# targetController.net
KiCad netlist of a schematic drawn in EAGLE
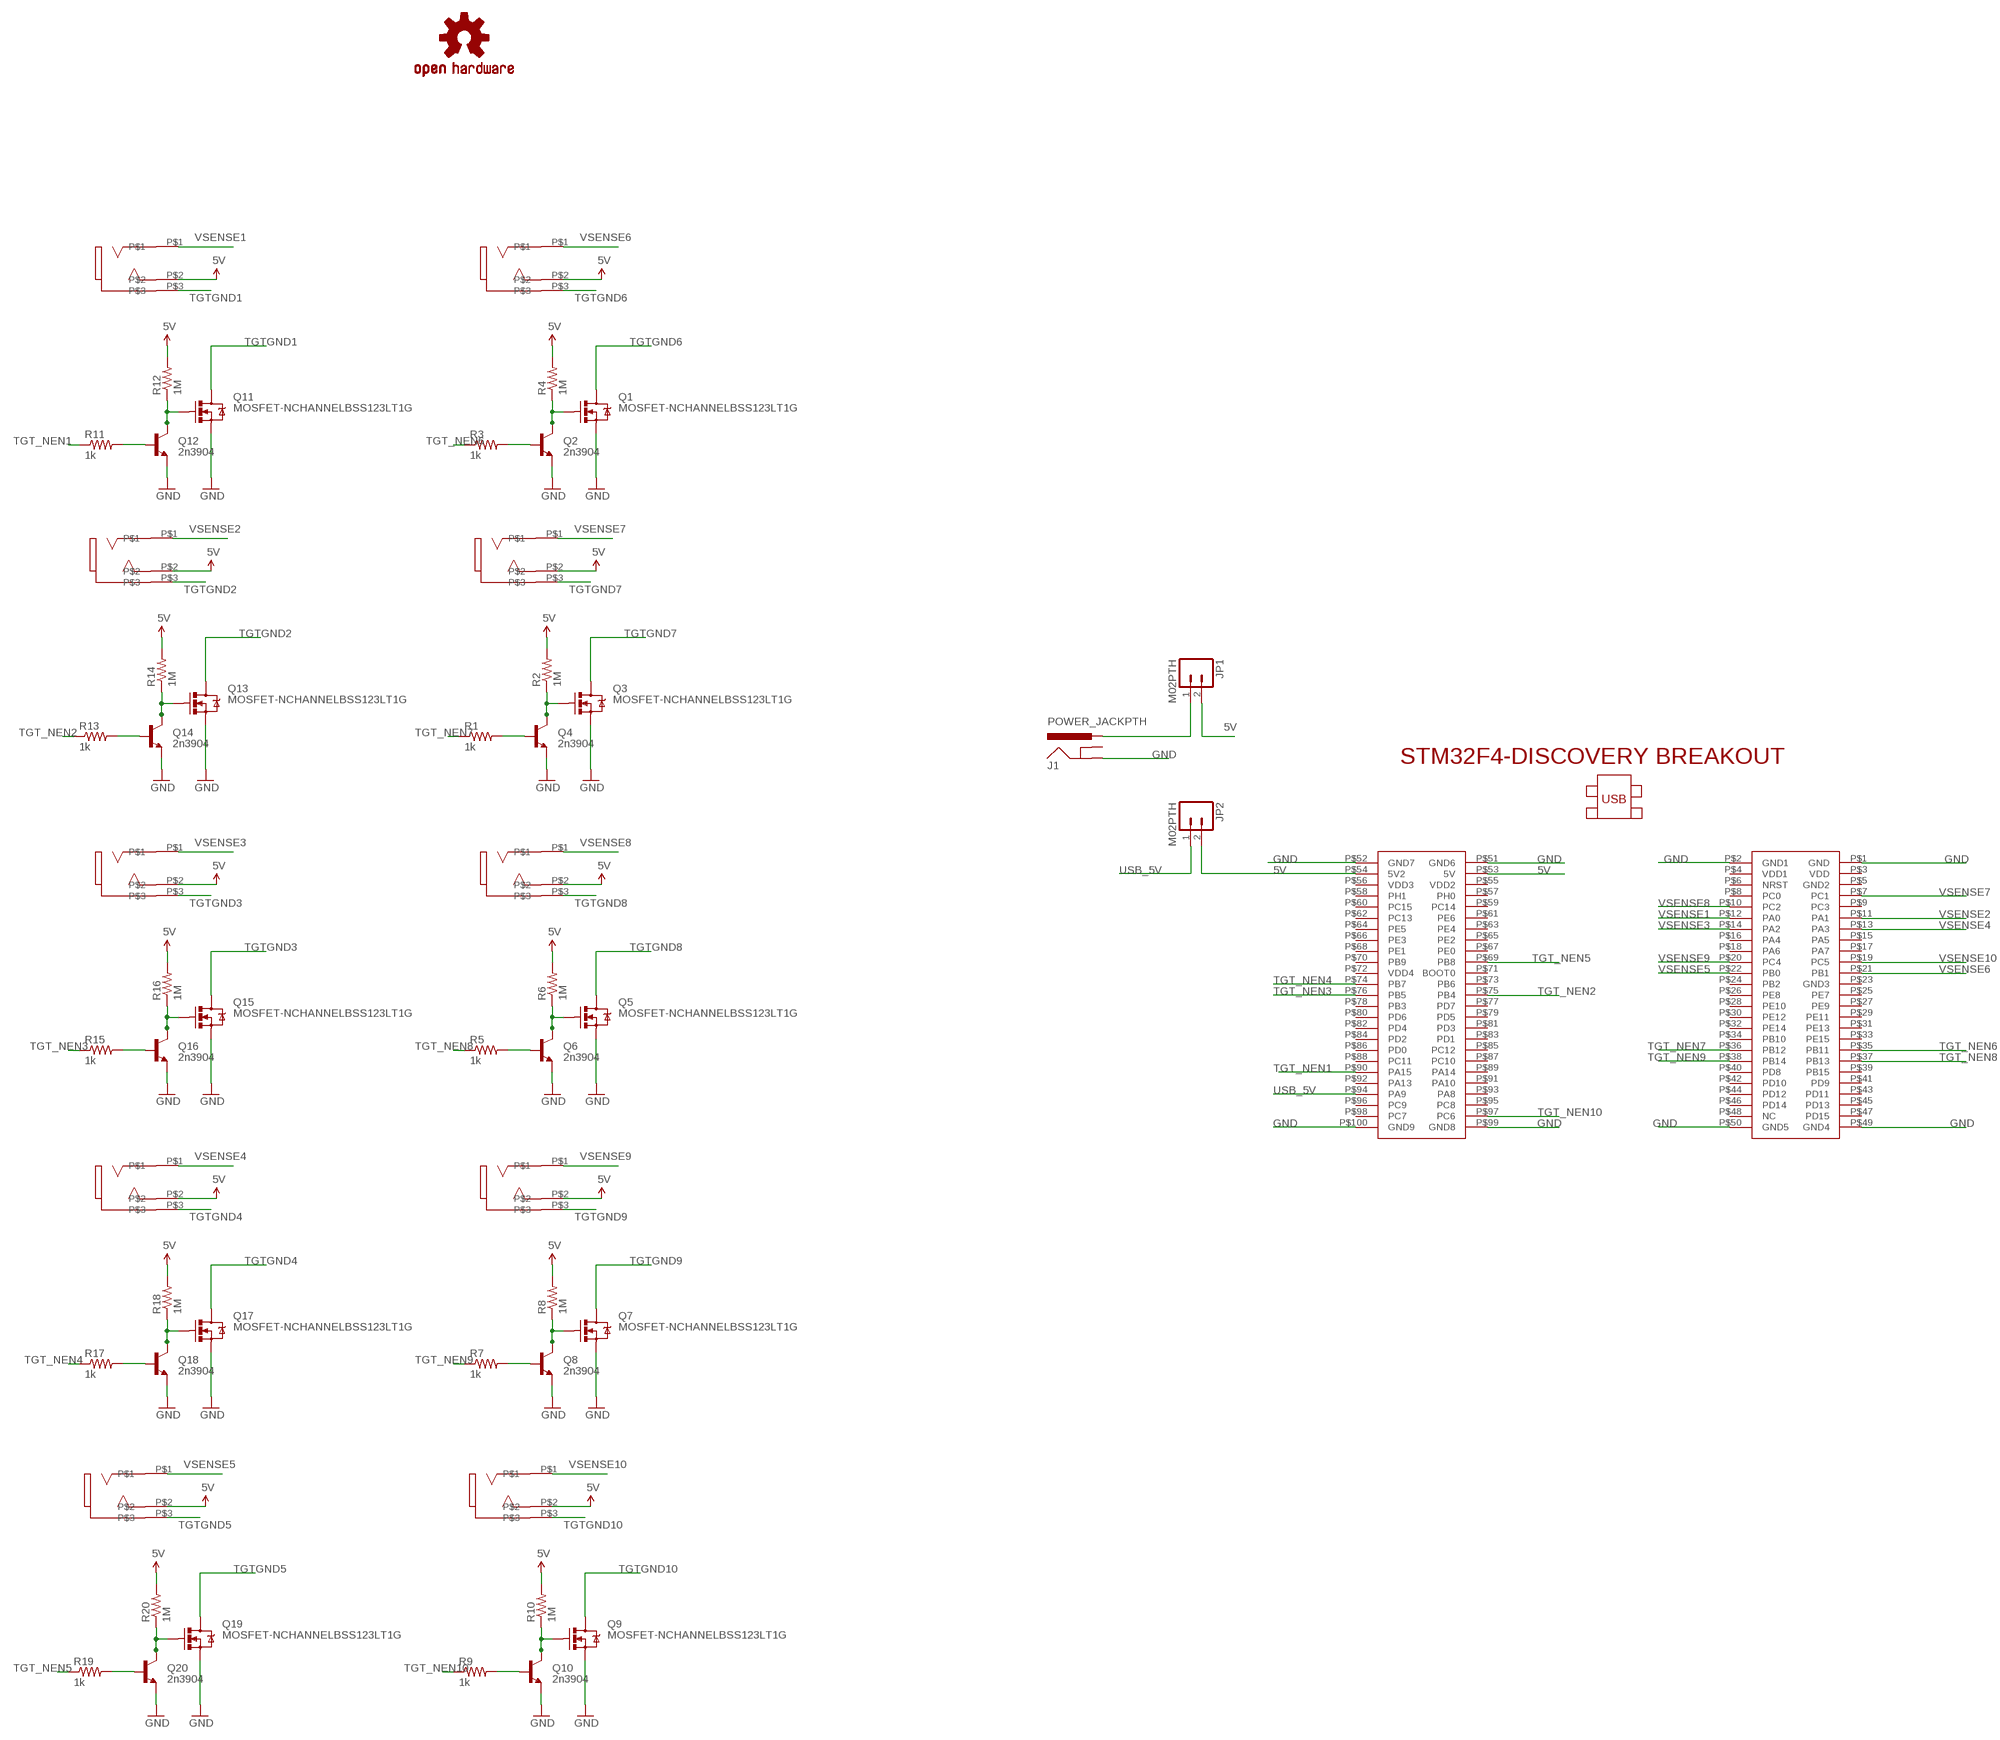
[diagram p0: schematic, sheet 1]

(export (version "E")
  (design (tool "Eeschema 10.0.6"))
  (components
    (comp (ref "J1")
      (value "POWER_JACKPTH")
      (footprint "eagle-import:POWER_JACK_PTH")
      (libsource (lib "eagle-import") (part "POWER_JACKPTH"))
    )
    (comp (ref "JP1")
      (value "M02PTH")
      (footprint "eagle-import:1X02")
      (libsource (lib "eagle-import") (part "M02PTH"))
    )
    (comp (ref "JP2")
      (value "M02PTH")
      (footprint "eagle-import:1X02")
      (libsource (lib "eagle-import") (part "M02PTH"))
    )
    (comp (ref "LOGO1")
      (value "OSHW-LOGOS")
      (footprint "eagle-import:OSHW-LOGO-S")
      (libsource (lib "eagle-import") (part "OSHW-LOGOS"))
    )
    (comp (ref "Q1")
      (value "MOSFET-NCHANNELBSS123LT1G")
      (footprint "eagle-import:SOT23")
      (libsource (lib "eagle-import") (part "MOSFET-NCHANNELBSS123LT1G"))
    )
    (comp (ref "Q2")
      (value "2n3904")
      (footprint "eagle-import:SOT23-3")
      (libsource (lib "eagle-import") (part "TRANSISTOR_NPNSOT23-3"))
    )
    (comp (ref "Q3")
      (value "MOSFET-NCHANNELBSS123LT1G")
      (footprint "eagle-import:SOT23")
      (libsource (lib "eagle-import") (part "MOSFET-NCHANNELBSS123LT1G"))
    )
    (comp (ref "Q4")
      (value "2n3904")
      (footprint "eagle-import:SOT23-3")
      (libsource (lib "eagle-import") (part "TRANSISTOR_NPNSOT23-3"))
    )
    (comp (ref "Q5")
      (value "MOSFET-NCHANNELBSS123LT1G")
      (footprint "eagle-import:SOT23")
      (libsource (lib "eagle-import") (part "MOSFET-NCHANNELBSS123LT1G"))
    )
    (comp (ref "Q6")
      (value "2n3904")
      (footprint "eagle-import:SOT23-3")
      (libsource (lib "eagle-import") (part "TRANSISTOR_NPNSOT23-3"))
    )
    (comp (ref "Q7")
      (value "MOSFET-NCHANNELBSS123LT1G")
      (footprint "eagle-import:SOT23")
      (libsource (lib "eagle-import") (part "MOSFET-NCHANNELBSS123LT1G"))
    )
    (comp (ref "Q8")
      (value "2n3904")
      (footprint "eagle-import:SOT23-3")
      (libsource (lib "eagle-import") (part "TRANSISTOR_NPNSOT23-3"))
    )
    (comp (ref "Q9")
      (value "MOSFET-NCHANNELBSS123LT1G")
      (footprint "eagle-import:SOT23")
      (libsource (lib "eagle-import") (part "MOSFET-NCHANNELBSS123LT1G"))
    )
    (comp (ref "Q10")
      (value "2n3904")
      (footprint "eagle-import:SOT23-3")
      (libsource (lib "eagle-import") (part "TRANSISTOR_NPNSOT23-3"))
    )
    (comp (ref "Q11")
      (value "MOSFET-NCHANNELBSS123LT1G")
      (footprint "eagle-import:SOT23")
      (libsource (lib "eagle-import") (part "MOSFET-NCHANNELBSS123LT1G"))
    )
    (comp (ref "Q12")
      (value "2n3904")
      (footprint "eagle-import:SOT23-3")
      (libsource (lib "eagle-import") (part "TRANSISTOR_NPNSOT23-3"))
    )
    (comp (ref "Q13")
      (value "MOSFET-NCHANNELBSS123LT1G")
      (footprint "eagle-import:SOT23")
      (libsource (lib "eagle-import") (part "MOSFET-NCHANNELBSS123LT1G"))
    )
    (comp (ref "Q14")
      (value "2n3904")
      (footprint "eagle-import:SOT23-3")
      (libsource (lib "eagle-import") (part "TRANSISTOR_NPNSOT23-3"))
    )
    (comp (ref "Q15")
      (value "MOSFET-NCHANNELBSS123LT1G")
      (footprint "eagle-import:SOT23")
      (libsource (lib "eagle-import") (part "MOSFET-NCHANNELBSS123LT1G"))
    )
    (comp (ref "Q16")
      (value "2n3904")
      (footprint "eagle-import:SOT23-3")
      (libsource (lib "eagle-import") (part "TRANSISTOR_NPNSOT23-3"))
    )
    (comp (ref "Q17")
      (value "MOSFET-NCHANNELBSS123LT1G")
      (footprint "eagle-import:SOT23")
      (libsource (lib "eagle-import") (part "MOSFET-NCHANNELBSS123LT1G"))
    )
    (comp (ref "Q18")
      (value "2n3904")
      (footprint "eagle-import:SOT23-3")
      (libsource (lib "eagle-import") (part "TRANSISTOR_NPNSOT23-3"))
    )
    (comp (ref "Q19")
      (value "MOSFET-NCHANNELBSS123LT1G")
      (footprint "eagle-import:SOT23")
      (libsource (lib "eagle-import") (part "MOSFET-NCHANNELBSS123LT1G"))
    )
    (comp (ref "Q20")
      (value "2n3904")
      (footprint "eagle-import:SOT23-3")
      (libsource (lib "eagle-import") (part "TRANSISTOR_NPNSOT23-3"))
    )
    (comp (ref "R1")
      (value "1k")
      (footprint "eagle-import:0805")
      (libsource (lib "eagle-import") (part "RESISTOR0805-RES"))
    )
    (comp (ref "R2")
      (value "1M")
      (footprint "eagle-import:0805")
      (libsource (lib "eagle-import") (part "RESISTOR0805-RES"))
    )
    (comp (ref "R3")
      (value "1k")
      (footprint "eagle-import:0805")
      (libsource (lib "eagle-import") (part "RESISTOR0805-RES"))
    )
    (comp (ref "R4")
      (value "1M")
      (footprint "eagle-import:0805")
      (libsource (lib "eagle-import") (part "RESISTOR0805-RES"))
    )
    (comp (ref "R5")
      (value "1k")
      (footprint "eagle-import:0805")
      (libsource (lib "eagle-import") (part "RESISTOR0805-RES"))
    )
    (comp (ref "R6")
      (value "1M")
      (footprint "eagle-import:0805")
      (libsource (lib "eagle-import") (part "RESISTOR0805-RES"))
    )
    (comp (ref "R7")
      (value "1k")
      (footprint "eagle-import:0805")
      (libsource (lib "eagle-import") (part "RESISTOR0805-RES"))
    )
    (comp (ref "R8")
      (value "1M")
      (footprint "eagle-import:0805")
      (libsource (lib "eagle-import") (part "RESISTOR0805-RES"))
    )
    (comp (ref "R9")
      (value "1k")
      (footprint "eagle-import:0805")
      (libsource (lib "eagle-import") (part "RESISTOR0805-RES"))
    )
    (comp (ref "R10")
      (value "1M")
      (footprint "eagle-import:0805")
      (libsource (lib "eagle-import") (part "RESISTOR0805-RES"))
    )
    (comp (ref "R11")
      (value "1k")
      (footprint "eagle-import:0805")
      (libsource (lib "eagle-import") (part "RESISTOR0805-RES"))
    )
    (comp (ref "R12")
      (value "1M")
      (footprint "eagle-import:0805")
      (libsource (lib "eagle-import") (part "RESISTOR0805-RES"))
    )
    (comp (ref "R13")
      (value "1k")
      (footprint "eagle-import:0805")
      (libsource (lib "eagle-import") (part "RESISTOR0805-RES"))
    )
    (comp (ref "R14")
      (value "1M")
      (footprint "eagle-import:0805")
      (libsource (lib "eagle-import") (part "RESISTOR0805-RES"))
    )
    (comp (ref "R15")
      (value "1k")
      (footprint "eagle-import:0805")
      (libsource (lib "eagle-import") (part "RESISTOR0805-RES"))
    )
    (comp (ref "R16")
      (value "1M")
      (footprint "eagle-import:0805")
      (libsource (lib "eagle-import") (part "RESISTOR0805-RES"))
    )
    (comp (ref "R17")
      (value "1k")
      (footprint "eagle-import:0805")
      (libsource (lib "eagle-import") (part "RESISTOR0805-RES"))
    )
    (comp (ref "R18")
      (value "1M")
      (footprint "eagle-import:0805")
      (libsource (lib "eagle-import") (part "RESISTOR0805-RES"))
    )
    (comp (ref "R19")
      (value "1k")
      (footprint "eagle-import:0805")
      (libsource (lib "eagle-import") (part "RESISTOR0805-RES"))
    )
    (comp (ref "R20")
      (value "1M")
      (footprint "eagle-import:0805")
      (libsource (lib "eagle-import") (part "RESISTOR0805-RES"))
    )
    (comp (ref "T1")
      (value "35RASMT2BHNTRX")
      (footprint "eagle-import:35RASMT2BHNTRX")
      (libsource (lib "eagle-import") (part "35RASMT2BHNTRX"))
    )
    (comp (ref "T2")
      (value "35RASMT2BHNTRX")
      (footprint "eagle-import:35RASMT2BHNTRX")
      (libsource (lib "eagle-import") (part "35RASMT2BHNTRX"))
    )
    (comp (ref "T3")
      (value "35RASMT2BHNTRX")
      (footprint "eagle-import:35RASMT2BHNTRX")
      (libsource (lib "eagle-import") (part "35RASMT2BHNTRX"))
    )
    (comp (ref "T4")
      (value "35RASMT2BHNTRX")
      (footprint "eagle-import:35RASMT2BHNTRX")
      (libsource (lib "eagle-import") (part "35RASMT2BHNTRX"))
    )
    (comp (ref "T5")
      (value "35RASMT2BHNTRX")
      (footprint "eagle-import:35RASMT2BHNTRX")
      (libsource (lib "eagle-import") (part "35RASMT2BHNTRX"))
    )
    (comp (ref "T6")
      (value "35RASMT2BHNTRX")
      (footprint "eagle-import:35RASMT2BHNTRX")
      (libsource (lib "eagle-import") (part "35RASMT2BHNTRX"))
    )
    (comp (ref "T7")
      (value "35RASMT2BHNTRX")
      (footprint "eagle-import:35RASMT2BHNTRX")
      (libsource (lib "eagle-import") (part "35RASMT2BHNTRX"))
    )
    (comp (ref "T8")
      (value "35RASMT2BHNTRX")
      (footprint "eagle-import:35RASMT2BHNTRX")
      (libsource (lib "eagle-import") (part "35RASMT2BHNTRX"))
    )
    (comp (ref "T9")
      (value "35RASMT2BHNTRX")
      (footprint "eagle-import:35RASMT2BHNTRX")
      (libsource (lib "eagle-import") (part "35RASMT2BHNTRX"))
    )
    (comp (ref "T10")
      (value "35RASMT2BHNTRX")
      (footprint "eagle-import:35RASMT2BHNTRX")
      (libsource (lib "eagle-import") (part "35RASMT2BHNTRX"))
    )
    (comp (ref "U$1")
      (value "STM32F4-DISCOVERY")
      (footprint "eagle-import:STM32F4-DISCOVERY")
      (libsource (lib "eagle-import") (part "STM32F4-DISCOVERY"))
    )
  )
  (nets
    (net (code "1") (name "/TGTGND1") (class "Default")
      (node (ref "Q11") (pin "3") (pinfunction "D_3") (pintype "passive"))
      (node (ref "T1") (pin "P$3") (pinfunction "P$3_P$3") (pintype "bidirectional"))
    )
    (net (code "2") (name "/TGTGND2") (class "Default")
      (node (ref "Q13") (pin "3") (pinfunction "D_3") (pintype "passive"))
      (node (ref "T2") (pin "P$3") (pinfunction "P$3_P$3") (pintype "bidirectional"))
    )
    (net (code "3") (name "/TGTGND3") (class "Default")
      (node (ref "Q15") (pin "3") (pinfunction "D_3") (pintype "passive"))
      (node (ref "T3") (pin "P$3") (pinfunction "P$3_P$3") (pintype "bidirectional"))
    )
    (net (code "4") (name "/TGTGND4") (class "Default")
      (node (ref "Q17") (pin "3") (pinfunction "D_3") (pintype "passive"))
      (node (ref "T4") (pin "P$3") (pinfunction "P$3_P$3") (pintype "bidirectional"))
    )
    (net (code "5") (name "/TGTGND5") (class "Default")
      (node (ref "Q19") (pin "3") (pinfunction "D_3") (pintype "passive"))
      (node (ref "T5") (pin "P$3") (pinfunction "P$3_P$3") (pintype "bidirectional"))
    )
    (net (code "6") (name "/TGTGND6") (class "Default")
      (node (ref "Q1") (pin "3") (pinfunction "D_3") (pintype "passive"))
      (node (ref "T6") (pin "P$3") (pinfunction "P$3_P$3") (pintype "bidirectional"))
    )
    (net (code "7") (name "/TGTGND7") (class "Default")
      (node (ref "Q3") (pin "3") (pinfunction "D_3") (pintype "passive"))
      (node (ref "T7") (pin "P$3") (pinfunction "P$3_P$3") (pintype "bidirectional"))
    )
    (net (code "8") (name "/TGTGND8") (class "Default")
      (node (ref "Q5") (pin "3") (pinfunction "D_3") (pintype "passive"))
      (node (ref "T8") (pin "P$3") (pinfunction "P$3_P$3") (pintype "bidirectional"))
    )
    (net (code "9") (name "/TGTGND9") (class "Default")
      (node (ref "Q7") (pin "3") (pinfunction "D_3") (pintype "passive"))
      (node (ref "T9") (pin "P$3") (pinfunction "P$3_P$3") (pintype "bidirectional"))
    )
    (net (code "10") (name "/TGTGND10") (class "Default")
      (node (ref "Q9") (pin "3") (pinfunction "D_3") (pintype "passive"))
      (node (ref "T10") (pin "P$3") (pinfunction "P$3_P$3") (pintype "bidirectional"))
    )
    (net (code "11") (name "/TGT_NEN1") (class "Default")
      (node (ref "R11") (pin "1") (pinfunction "1_1") (pintype "passive"))
      (node (ref "U$1") (pin "P$90") (pinfunction "PA15_P$90") (pintype "bidirectional"))
    )
    (net (code "12") (name "/TGT_NEN2") (class "Default")
      (node (ref "R13") (pin "1") (pinfunction "1_1") (pintype "passive"))
      (node (ref "U$1") (pin "P$75") (pinfunction "PB4_P$75") (pintype "bidirectional"))
    )
    (net (code "13") (name "/TGT_NEN3") (class "Default")
      (node (ref "R15") (pin "1") (pinfunction "1_1") (pintype "passive"))
      (node (ref "U$1") (pin "P$76") (pinfunction "PB5_P$76") (pintype "bidirectional"))
    )
    (net (code "14") (name "/TGT_NEN4") (class "Default")
      (node (ref "R17") (pin "1") (pinfunction "1_1") (pintype "passive"))
      (node (ref "U$1") (pin "P$74") (pinfunction "PB7_P$74") (pintype "bidirectional"))
    )
    (net (code "15") (name "/TGT_NEN5") (class "Default")
      (node (ref "R19") (pin "1") (pinfunction "1_1") (pintype "passive"))
      (node (ref "U$1") (pin "P$69") (pinfunction "PB8_P$69") (pintype "bidirectional"))
    )
    (net (code "16") (name "/TGT_NEN6") (class "Default")
      (node (ref "R3") (pin "1") (pinfunction "1_1") (pintype "passive"))
      (node (ref "U$1") (pin "P$35") (pinfunction "PB11_P$35") (pintype "bidirectional"))
    )
    (net (code "17") (name "/TGT_NEN7") (class "Default")
      (node (ref "R1") (pin "1") (pinfunction "1_1") (pintype "passive"))
      (node (ref "U$1") (pin "P$36") (pinfunction "PB12_P$36") (pintype "bidirectional"))
    )
    (net (code "18") (name "/TGT_NEN8") (class "Default")
      (node (ref "R5") (pin "1") (pinfunction "1_1") (pintype "passive"))
      (node (ref "U$1") (pin "P$37") (pinfunction "PB13_P$37") (pintype "bidirectional"))
    )
    (net (code "19") (name "/TGT_NEN9") (class "Default")
      (node (ref "R7") (pin "1") (pinfunction "1_1") (pintype "passive"))
      (node (ref "U$1") (pin "P$38") (pinfunction "PB14_P$38") (pintype "bidirectional"))
    )
    (net (code "20") (name "/TGT_NEN10") (class "Default")
      (node (ref "R9") (pin "1") (pinfunction "1_1") (pintype "passive"))
      (node (ref "U$1") (pin "P$97") (pinfunction "PC6_P$97") (pintype "bidirectional"))
    )
    (net (code "21") (name "/USB_5V") (class "Default")
      (node (ref "JP2") (pin "1") (pinfunction "1_1") (pintype "passive"))
      (node (ref "U$1") (pin "P$94") (pinfunction "PA9_P$94") (pintype "bidirectional"))
    )
    (net (code "22") (name "/VSENSE1") (class "Default")
      (node (ref "T1") (pin "P$1") (pinfunction "P$1_P$1") (pintype "bidirectional"))
      (node (ref "U$1") (pin "P$12") (pinfunction "PA0_P$12") (pintype "bidirectional"))
    )
    (net (code "23") (name "/VSENSE2") (class "Default")
      (node (ref "T2") (pin "P$1") (pinfunction "P$1_P$1") (pintype "bidirectional"))
      (node (ref "U$1") (pin "P$11") (pinfunction "PA1_P$11") (pintype "bidirectional"))
    )
    (net (code "24") (name "/VSENSE3") (class "Default")
      (node (ref "T3") (pin "P$1") (pinfunction "P$1_P$1") (pintype "bidirectional"))
      (node (ref "U$1") (pin "P$14") (pinfunction "PA2_P$14") (pintype "bidirectional"))
    )
    (net (code "25") (name "/VSENSE4") (class "Default")
      (node (ref "T4") (pin "P$1") (pinfunction "P$1_P$1") (pintype "bidirectional"))
      (node (ref "U$1") (pin "P$13") (pinfunction "PA3_P$13") (pintype "bidirectional"))
    )
    (net (code "26") (name "/VSENSE5") (class "Default")
      (node (ref "T5") (pin "P$1") (pinfunction "P$1_P$1") (pintype "bidirectional"))
      (node (ref "U$1") (pin "P$22") (pinfunction "PB0_P$22") (pintype "bidirectional"))
    )
    (net (code "27") (name "/VSENSE6") (class "Default")
      (node (ref "T6") (pin "P$1") (pinfunction "P$1_P$1") (pintype "bidirectional"))
      (node (ref "U$1") (pin "P$21") (pinfunction "PB1_P$21") (pintype "bidirectional"))
    )
    (net (code "28") (name "/VSENSE7") (class "Default")
      (node (ref "T7") (pin "P$1") (pinfunction "P$1_P$1") (pintype "bidirectional"))
      (node (ref "U$1") (pin "P$7") (pinfunction "PC1_P$7") (pintype "bidirectional"))
    )
    (net (code "29") (name "/VSENSE8") (class "Default")
      (node (ref "T8") (pin "P$1") (pinfunction "P$1_P$1") (pintype "bidirectional"))
      (node (ref "U$1") (pin "P$10") (pinfunction "PC2_P$10") (pintype "bidirectional"))
    )
    (net (code "30") (name "/VSENSE9") (class "Default")
      (node (ref "T9") (pin "P$1") (pinfunction "P$1_P$1") (pintype "bidirectional"))
      (node (ref "U$1") (pin "P$20") (pinfunction "PC4_P$20") (pintype "bidirectional"))
    )
    (net (code "31") (name "/VSENSE10") (class "Default")
      (node (ref "T10") (pin "P$1") (pinfunction "P$1_P$1") (pintype "bidirectional"))
      (node (ref "U$1") (pin "P$19") (pinfunction "PC5_P$19") (pintype "bidirectional"))
    )
    (net (code "32") (name "5V") (class "Default")
      (node (ref "JP1") (pin "2") (pinfunction "2_2") (pintype "passive"))
      (node (ref "JP2") (pin "2") (pinfunction "2_2") (pintype "passive"))
      (node (ref "R10") (pin "2") (pinfunction "2_2") (pintype "passive"))
      (node (ref "R12") (pin "2") (pinfunction "2_2") (pintype "passive"))
      (node (ref "R14") (pin "2") (pinfunction "2_2") (pintype "passive"))
      (node (ref "R16") (pin "2") (pinfunction "2_2") (pintype "passive"))
      (node (ref "R18") (pin "2") (pinfunction "2_2") (pintype "passive"))
      (node (ref "R2") (pin "2") (pinfunction "2_2") (pintype "passive"))
      (node (ref "R20") (pin "2") (pinfunction "2_2") (pintype "passive"))
      (node (ref "R4") (pin "2") (pinfunction "2_2") (pintype "passive"))
      (node (ref "R6") (pin "2") (pinfunction "2_2") (pintype "passive"))
      (node (ref "R8") (pin "2") (pinfunction "2_2") (pintype "passive"))
      (node (ref "T1") (pin "P$2") (pinfunction "P$2_P$2") (pintype "bidirectional"))
      (node (ref "T10") (pin "P$2") (pinfunction "P$2_P$2") (pintype "bidirectional"))
      (node (ref "T2") (pin "P$2") (pinfunction "P$2_P$2") (pintype "bidirectional"))
      (node (ref "T3") (pin "P$2") (pinfunction "P$2_P$2") (pintype "bidirectional"))
      (node (ref "T4") (pin "P$2") (pinfunction "P$2_P$2") (pintype "bidirectional"))
      (node (ref "T5") (pin "P$2") (pinfunction "P$2_P$2") (pintype "bidirectional"))
      (node (ref "T6") (pin "P$2") (pinfunction "P$2_P$2") (pintype "bidirectional"))
      (node (ref "T7") (pin "P$2") (pinfunction "P$2_P$2") (pintype "bidirectional"))
      (node (ref "T8") (pin "P$2") (pinfunction "P$2_P$2") (pintype "bidirectional"))
      (node (ref "T9") (pin "P$2") (pinfunction "P$2_P$2") (pintype "bidirectional"))
      (node (ref "U$1") (pin "P$53") (pinfunction "5V_P$53") (pintype "bidirectional"))
      (node (ref "U$1") (pin "P$54") (pinfunction "5V2_P$54") (pintype "bidirectional"))
    )
    (net (code "33") (name "GND") (class "Default")
      (node (ref "J1") (pin "GND") (pinfunction "GND_GND") (pintype "bidirectional"))
      (node (ref "Q1") (pin "2") (pinfunction "S_2") (pintype "passive"))
      (node (ref "Q10") (pin "2") (pinfunction "E_2") (pintype "passive"))
      (node (ref "Q11") (pin "2") (pinfunction "S_2") (pintype "passive"))
      (node (ref "Q12") (pin "2") (pinfunction "E_2") (pintype "passive"))
      (node (ref "Q13") (pin "2") (pinfunction "S_2") (pintype "passive"))
      (node (ref "Q14") (pin "2") (pinfunction "E_2") (pintype "passive"))
      (node (ref "Q15") (pin "2") (pinfunction "S_2") (pintype "passive"))
      (node (ref "Q16") (pin "2") (pinfunction "E_2") (pintype "passive"))
      (node (ref "Q17") (pin "2") (pinfunction "S_2") (pintype "passive"))
      (node (ref "Q18") (pin "2") (pinfunction "E_2") (pintype "passive"))
      (node (ref "Q19") (pin "2") (pinfunction "S_2") (pintype "passive"))
      (node (ref "Q2") (pin "2") (pinfunction "E_2") (pintype "passive"))
      (node (ref "Q20") (pin "2") (pinfunction "E_2") (pintype "passive"))
      (node (ref "Q3") (pin "2") (pinfunction "S_2") (pintype "passive"))
      (node (ref "Q4") (pin "2") (pinfunction "E_2") (pintype "passive"))
      (node (ref "Q5") (pin "2") (pinfunction "S_2") (pintype "passive"))
      (node (ref "Q6") (pin "2") (pinfunction "E_2") (pintype "passive"))
      (node (ref "Q7") (pin "2") (pinfunction "S_2") (pintype "passive"))
      (node (ref "Q8") (pin "2") (pinfunction "E_2") (pintype "passive"))
      (node (ref "Q9") (pin "2") (pinfunction "S_2") (pintype "passive"))
      (node (ref "U$1") (pin "P$1") (pinfunction "GND_P$1") (pintype "bidirectional"))
      (node (ref "U$1") (pin "P$100") (pinfunction "GND9_P$100") (pintype "bidirectional"))
      (node (ref "U$1") (pin "P$2") (pinfunction "GND1_P$2") (pintype "bidirectional"))
      (node (ref "U$1") (pin "P$49") (pinfunction "GND4_P$49") (pintype "bidirectional"))
      (node (ref "U$1") (pin "P$50") (pinfunction "GND5_P$50") (pintype "bidirectional"))
      (node (ref "U$1") (pin "P$51") (pinfunction "GND6_P$51") (pintype "bidirectional"))
      (node (ref "U$1") (pin "P$52") (pinfunction "GND7_P$52") (pintype "bidirectional"))
      (node (ref "U$1") (pin "P$99") (pinfunction "GND8_P$99") (pintype "bidirectional"))
    )
    (net (code "34") (name "Net-(J1-PadPWR)") (class "Default")
      (node (ref "J1") (pin "PWR") (pinfunction "PWR_PWR") (pintype "bidirectional"))
      (node (ref "JP1") (pin "1") (pinfunction "1_1") (pintype "passive"))
    )
    (net (code "35") (name "Net-(Q1-G)") (class "Default")
      (node (ref "Q1") (pin "1") (pinfunction "G_1") (pintype "passive"))
      (node (ref "Q2") (pin "3") (pinfunction "C_3") (pintype "passive"))
      (node (ref "R4") (pin "1") (pinfunction "1_1") (pintype "passive"))
    )
    (net (code "36") (name "Net-(Q2-B)") (class "Default")
      (node (ref "Q2") (pin "1") (pinfunction "B_1") (pintype "passive"))
      (node (ref "R3") (pin "2") (pinfunction "2_2") (pintype "passive"))
    )
    (net (code "37") (name "Net-(Q3-G)") (class "Default")
      (node (ref "Q3") (pin "1") (pinfunction "G_1") (pintype "passive"))
      (node (ref "Q4") (pin "3") (pinfunction "C_3") (pintype "passive"))
      (node (ref "R2") (pin "1") (pinfunction "1_1") (pintype "passive"))
    )
    (net (code "38") (name "Net-(Q4-B)") (class "Default")
      (node (ref "Q4") (pin "1") (pinfunction "B_1") (pintype "passive"))
      (node (ref "R1") (pin "2") (pinfunction "2_2") (pintype "passive"))
    )
    (net (code "39") (name "Net-(Q5-G)") (class "Default")
      (node (ref "Q5") (pin "1") (pinfunction "G_1") (pintype "passive"))
      (node (ref "Q6") (pin "3") (pinfunction "C_3") (pintype "passive"))
      (node (ref "R6") (pin "1") (pinfunction "1_1") (pintype "passive"))
    )
    (net (code "40") (name "Net-(Q6-B)") (class "Default")
      (node (ref "Q6") (pin "1") (pinfunction "B_1") (pintype "passive"))
      (node (ref "R5") (pin "2") (pinfunction "2_2") (pintype "passive"))
    )
    (net (code "41") (name "Net-(Q7-G)") (class "Default")
      (node (ref "Q7") (pin "1") (pinfunction "G_1") (pintype "passive"))
      (node (ref "Q8") (pin "3") (pinfunction "C_3") (pintype "passive"))
      (node (ref "R8") (pin "1") (pinfunction "1_1") (pintype "passive"))
    )
    (net (code "42") (name "Net-(Q8-B)") (class "Default")
      (node (ref "Q8") (pin "1") (pinfunction "B_1") (pintype "passive"))
      (node (ref "R7") (pin "2") (pinfunction "2_2") (pintype "passive"))
    )
    (net (code "43") (name "Net-(Q10-B)") (class "Default")
      (node (ref "Q10") (pin "1") (pinfunction "B_1") (pintype "passive"))
      (node (ref "R9") (pin "2") (pinfunction "2_2") (pintype "passive"))
    )
    (net (code "44") (name "Net-(Q10-C)") (class "Default")
      (node (ref "Q10") (pin "3") (pinfunction "C_3") (pintype "passive"))
      (node (ref "Q9") (pin "1") (pinfunction "G_1") (pintype "passive"))
      (node (ref "R10") (pin "1") (pinfunction "1_1") (pintype "passive"))
    )
    (net (code "45") (name "Net-(Q11-G)") (class "Default")
      (node (ref "Q11") (pin "1") (pinfunction "G_1") (pintype "passive"))
      (node (ref "Q12") (pin "3") (pinfunction "C_3") (pintype "passive"))
      (node (ref "R12") (pin "1") (pinfunction "1_1") (pintype "passive"))
    )
    (net (code "46") (name "Net-(Q12-B)") (class "Default")
      (node (ref "Q12") (pin "1") (pinfunction "B_1") (pintype "passive"))
      (node (ref "R11") (pin "2") (pinfunction "2_2") (pintype "passive"))
    )
    (net (code "47") (name "Net-(Q13-G)") (class "Default")
      (node (ref "Q13") (pin "1") (pinfunction "G_1") (pintype "passive"))
      (node (ref "Q14") (pin "3") (pinfunction "C_3") (pintype "passive"))
      (node (ref "R14") (pin "1") (pinfunction "1_1") (pintype "passive"))
    )
    (net (code "48") (name "Net-(Q14-B)") (class "Default")
      (node (ref "Q14") (pin "1") (pinfunction "B_1") (pintype "passive"))
      (node (ref "R13") (pin "2") (pinfunction "2_2") (pintype "passive"))
    )
    (net (code "49") (name "Net-(Q15-G)") (class "Default")
      (node (ref "Q15") (pin "1") (pinfunction "G_1") (pintype "passive"))
      (node (ref "Q16") (pin "3") (pinfunction "C_3") (pintype "passive"))
      (node (ref "R16") (pin "1") (pinfunction "1_1") (pintype "passive"))
    )
    (net (code "50") (name "Net-(Q16-B)") (class "Default")
      (node (ref "Q16") (pin "1") (pinfunction "B_1") (pintype "passive"))
      (node (ref "R15") (pin "2") (pinfunction "2_2") (pintype "passive"))
    )
    (net (code "51") (name "Net-(Q17-G)") (class "Default")
      (node (ref "Q17") (pin "1") (pinfunction "G_1") (pintype "passive"))
      (node (ref "Q18") (pin "3") (pinfunction "C_3") (pintype "passive"))
      (node (ref "R18") (pin "1") (pinfunction "1_1") (pintype "passive"))
    )
    (net (code "52") (name "Net-(Q18-B)") (class "Default")
      (node (ref "Q18") (pin "1") (pinfunction "B_1") (pintype "passive"))
      (node (ref "R17") (pin "2") (pinfunction "2_2") (pintype "passive"))
    )
    (net (code "53") (name "Net-(Q19-G)") (class "Default")
      (node (ref "Q19") (pin "1") (pinfunction "G_1") (pintype "passive"))
      (node (ref "Q20") (pin "3") (pinfunction "C_3") (pintype "passive"))
      (node (ref "R20") (pin "1") (pinfunction "1_1") (pintype "passive"))
    )
    (net (code "54") (name "Net-(Q20-B)") (class "Default")
      (node (ref "Q20") (pin "1") (pinfunction "B_1") (pintype "passive"))
      (node (ref "R19") (pin "2") (pinfunction "2_2") (pintype "passive"))
    )
    (net (code "55") (name "unconnected-(J1-PadGNDBREAK)") (class "Default")
      (node (ref "J1") (pin "GNDBREAK") (pinfunction "GNDBREAK_GNDBREAK") (pintype "bidirectional"))
    )
    (net (code "56") (name "unconnected-(U$1-BOOT0-PadP$71)") (class "Default")
      (node (ref "U$1") (pin "P$71") (pinfunction "BOOT0_P$71") (pintype "bidirectional"))
    )
    (net (code "57") (name "unconnected-(U$1-GND2-PadP$5)") (class "Default")
      (node (ref "U$1") (pin "P$5") (pinfunction "GND2_P$5") (pintype "bidirectional"))
    )
    (net (code "58") (name "unconnected-(U$1-GND3-PadP$23)") (class "Default")
      (node (ref "U$1") (pin "P$23") (pinfunction "GND3_P$23") (pintype "bidirectional"))
    )
    (net (code "59") (name "unconnected-(U$1-NC-PadP$48)") (class "Default")
      (node (ref "U$1") (pin "P$48") (pinfunction "NC_P$48") (pintype "bidirectional"))
    )
    (net (code "60") (name "unconnected-(U$1-NRST-PadP$6)") (class "Default")
      (node (ref "U$1") (pin "P$6") (pinfunction "NRST_P$6") (pintype "bidirectional"))
    )
    (net (code "61") (name "unconnected-(U$1-PA4-PadP$16)") (class "Default")
      (node (ref "U$1") (pin "P$16") (pinfunction "PA4_P$16") (pintype "bidirectional"))
    )
    (net (code "62") (name "unconnected-(U$1-PA5-PadP$15)") (class "Default")
      (node (ref "U$1") (pin "P$15") (pinfunction "PA5_P$15") (pintype "bidirectional"))
    )
    (net (code "63") (name "unconnected-(U$1-PA6-PadP$18)") (class "Default")
      (node (ref "U$1") (pin "P$18") (pinfunction "PA6_P$18") (pintype "bidirectional"))
    )
    (net (code "64") (name "unconnected-(U$1-PA7-PadP$17)") (class "Default")
      (node (ref "U$1") (pin "P$17") (pinfunction "PA7_P$17") (pintype "bidirectional"))
    )
    (net (code "65") (name "unconnected-(U$1-PA8-PadP$93)") (class "Default")
      (node (ref "U$1") (pin "P$93") (pinfunction "PA8_P$93") (pintype "bidirectional"))
    )
    (net (code "66") (name "unconnected-(U$1-PA10-PadP$91)") (class "Default")
      (node (ref "U$1") (pin "P$91") (pinfunction "PA10_P$91") (pintype "bidirectional"))
    )
    (net (code "67") (name "unconnected-(U$1-PA13-PadP$92)") (class "Default")
      (node (ref "U$1") (pin "P$92") (pinfunction "PA13_P$92") (pintype "bidirectional"))
    )
    (net (code "68") (name "unconnected-(U$1-PA14-PadP$89)") (class "Default")
      (node (ref "U$1") (pin "P$89") (pinfunction "PA14_P$89") (pintype "bidirectional"))
    )
    (net (code "69") (name "unconnected-(U$1-PB2-PadP$24)") (class "Default")
      (node (ref "U$1") (pin "P$24") (pinfunction "PB2_P$24") (pintype "bidirectional"))
    )
    (net (code "70") (name "unconnected-(U$1-PB3-PadP$78)") (class "Default")
      (node (ref "U$1") (pin "P$78") (pinfunction "PB3_P$78") (pintype "bidirectional"))
    )
    (net (code "71") (name "unconnected-(U$1-PB6-PadP$73)") (class "Default")
      (node (ref "U$1") (pin "P$73") (pinfunction "PB6_P$73") (pintype "bidirectional"))
    )
    (net (code "72") (name "unconnected-(U$1-PB9-PadP$70)") (class "Default")
      (node (ref "U$1") (pin "P$70") (pinfunction "PB9_P$70") (pintype "bidirectional"))
    )
    (net (code "73") (name "unconnected-(U$1-PB10-PadP$34)") (class "Default")
      (node (ref "U$1") (pin "P$34") (pinfunction "PB10_P$34") (pintype "bidirectional"))
    )
    (net (code "74") (name "unconnected-(U$1-PB15-PadP$39)") (class "Default")
      (node (ref "U$1") (pin "P$39") (pinfunction "PB15_P$39") (pintype "bidirectional"))
    )
    (net (code "75") (name "unconnected-(U$1-PC0-PadP$8)") (class "Default")
      (node (ref "U$1") (pin "P$8") (pinfunction "PC0_P$8") (pintype "bidirectional"))
    )
    (net (code "76") (name "unconnected-(U$1-PC3-PadP$9)") (class "Default")
      (node (ref "U$1") (pin "P$9") (pinfunction "PC3_P$9") (pintype "bidirectional"))
    )
    (net (code "77") (name "unconnected-(U$1-PC7-PadP$98)") (class "Default")
      (node (ref "U$1") (pin "P$98") (pinfunction "PC7_P$98") (pintype "bidirectional"))
    )
    (net (code "78") (name "unconnected-(U$1-PC8-PadP$95)") (class "Default")
      (node (ref "U$1") (pin "P$95") (pinfunction "PC8_P$95") (pintype "bidirectional"))
    )
    (net (code "79") (name "unconnected-(U$1-PC9-PadP$96)") (class "Default")
      (node (ref "U$1") (pin "P$96") (pinfunction "PC9_P$96") (pintype "bidirectional"))
    )
    (net (code "80") (name "unconnected-(U$1-PC10-PadP$87)") (class "Default")
      (node (ref "U$1") (pin "P$87") (pinfunction "PC10_P$87") (pintype "bidirectional"))
    )
    (net (code "81") (name "unconnected-(U$1-PC11-PadP$88)") (class "Default")
      (node (ref "U$1") (pin "P$88") (pinfunction "PC11_P$88") (pintype "bidirectional"))
    )
    (net (code "82") (name "unconnected-(U$1-PC12-PadP$85)") (class "Default")
      (node (ref "U$1") (pin "P$85") (pinfunction "PC12_P$85") (pintype "bidirectional"))
    )
    (net (code "83") (name "unconnected-(U$1-PC13-PadP$62)") (class "Default")
      (node (ref "U$1") (pin "P$62") (pinfunction "PC13_P$62") (pintype "bidirectional"))
    )
    (net (code "84") (name "unconnected-(U$1-PC14-PadP$59)") (class "Default")
      (node (ref "U$1") (pin "P$59") (pinfunction "PC14_P$59") (pintype "bidirectional"))
    )
    (net (code "85") (name "unconnected-(U$1-PC15-PadP$60)") (class "Default")
      (node (ref "U$1") (pin "P$60") (pinfunction "PC15_P$60") (pintype "bidirectional"))
    )
    (net (code "86") (name "unconnected-(U$1-PD0-PadP$86)") (class "Default")
      (node (ref "U$1") (pin "P$86") (pinfunction "PD0_P$86") (pintype "bidirectional"))
    )
    (net (code "87") (name "unconnected-(U$1-PD1-PadP$83)") (class "Default")
      (node (ref "U$1") (pin "P$83") (pinfunction "PD1_P$83") (pintype "bidirectional"))
    )
    (net (code "88") (name "unconnected-(U$1-PD2-PadP$84)") (class "Default")
      (node (ref "U$1") (pin "P$84") (pinfunction "PD2_P$84") (pintype "bidirectional"))
    )
    (net (code "89") (name "unconnected-(U$1-PD3-PadP$81)") (class "Default")
      (node (ref "U$1") (pin "P$81") (pinfunction "PD3_P$81") (pintype "bidirectional"))
    )
    (net (code "90") (name "unconnected-(U$1-PD4-PadP$82)") (class "Default")
      (node (ref "U$1") (pin "P$82") (pinfunction "PD4_P$82") (pintype "bidirectional"))
    )
    (net (code "91") (name "unconnected-(U$1-PD5-PadP$79)") (class "Default")
      (node (ref "U$1") (pin "P$79") (pinfunction "PD5_P$79") (pintype "bidirectional"))
    )
    (net (code "92") (name "unconnected-(U$1-PD6-PadP$80)") (class "Default")
      (node (ref "U$1") (pin "P$80") (pinfunction "PD6_P$80") (pintype "bidirectional"))
    )
    (net (code "93") (name "unconnected-(U$1-PD7-PadP$77)") (class "Default")
      (node (ref "U$1") (pin "P$77") (pinfunction "PD7_P$77") (pintype "bidirectional"))
    )
    (net (code "94") (name "unconnected-(U$1-PD8-PadP$40)") (class "Default")
      (node (ref "U$1") (pin "P$40") (pinfunction "PD8_P$40") (pintype "bidirectional"))
    )
    (net (code "95") (name "unconnected-(U$1-PD9-PadP$41)") (class "Default")
      (node (ref "U$1") (pin "P$41") (pinfunction "PD9_P$41") (pintype "bidirectional"))
    )
    (net (code "96") (name "unconnected-(U$1-PD10-PadP$42)") (class "Default")
      (node (ref "U$1") (pin "P$42") (pinfunction "PD10_P$42") (pintype "bidirectional"))
    )
    (net (code "97") (name "unconnected-(U$1-PD11-PadP$43)") (class "Default")
      (node (ref "U$1") (pin "P$43") (pinfunction "PD11_P$43") (pintype "bidirectional"))
    )
    (net (code "98") (name "unconnected-(U$1-PD12-PadP$44)") (class "Default")
      (node (ref "U$1") (pin "P$44") (pinfunction "PD12_P$44") (pintype "bidirectional"))
    )
    (net (code "99") (name "unconnected-(U$1-PD13-PadP$45)") (class "Default")
      (node (ref "U$1") (pin "P$45") (pinfunction "PD13_P$45") (pintype "bidirectional"))
    )
    (net (code "100") (name "unconnected-(U$1-PD14-PadP$46)") (class "Default")
      (node (ref "U$1") (pin "P$46") (pinfunction "PD14_P$46") (pintype "bidirectional"))
    )
    (net (code "101") (name "unconnected-(U$1-PD15-PadP$47)") (class "Default")
      (node (ref "U$1") (pin "P$47") (pinfunction "PD15_P$47") (pintype "bidirectional"))
    )
    (net (code "102") (name "unconnected-(U$1-PE0-PadP$67)") (class "Default")
      (node (ref "U$1") (pin "P$67") (pinfunction "PE0_P$67") (pintype "bidirectional"))
    )
    (net (code "103") (name "unconnected-(U$1-PE1-PadP$68)") (class "Default")
      (node (ref "U$1") (pin "P$68") (pinfunction "PE1_P$68") (pintype "bidirectional"))
    )
    (net (code "104") (name "unconnected-(U$1-PE2-PadP$65)") (class "Default")
      (node (ref "U$1") (pin "P$65") (pinfunction "PE2_P$65") (pintype "bidirectional"))
    )
    (net (code "105") (name "unconnected-(U$1-PE3-PadP$66)") (class "Default")
      (node (ref "U$1") (pin "P$66") (pinfunction "PE3_P$66") (pintype "bidirectional"))
    )
    (net (code "106") (name "unconnected-(U$1-PE4-PadP$63)") (class "Default")
      (node (ref "U$1") (pin "P$63") (pinfunction "PE4_P$63") (pintype "bidirectional"))
    )
    (net (code "107") (name "unconnected-(U$1-PE5-PadP$64)") (class "Default")
      (node (ref "U$1") (pin "P$64") (pinfunction "PE5_P$64") (pintype "bidirectional"))
    )
    (net (code "108") (name "unconnected-(U$1-PE6-PadP$61)") (class "Default")
      (node (ref "U$1") (pin "P$61") (pinfunction "PE6_P$61") (pintype "bidirectional"))
    )
    (net (code "109") (name "unconnected-(U$1-PE7-PadP$25)") (class "Default")
      (node (ref "U$1") (pin "P$25") (pinfunction "PE7_P$25") (pintype "bidirectional"))
    )
    (net (code "110") (name "unconnected-(U$1-PE8-PadP$26)") (class "Default")
      (node (ref "U$1") (pin "P$26") (pinfunction "PE8_P$26") (pintype "bidirectional"))
    )
    (net (code "111") (name "unconnected-(U$1-PE9-PadP$27)") (class "Default")
      (node (ref "U$1") (pin "P$27") (pinfunction "PE9_P$27") (pintype "bidirectional"))
    )
    (net (code "112") (name "unconnected-(U$1-PE10-PadP$28)") (class "Default")
      (node (ref "U$1") (pin "P$28") (pinfunction "PE10_P$28") (pintype "bidirectional"))
    )
    (net (code "113") (name "unconnected-(U$1-PE11-PadP$29)") (class "Default")
      (node (ref "U$1") (pin "P$29") (pinfunction "PE11_P$29") (pintype "bidirectional"))
    )
    (net (code "114") (name "unconnected-(U$1-PE12-PadP$30)") (class "Default")
      (node (ref "U$1") (pin "P$30") (pinfunction "PE12_P$30") (pintype "bidirectional"))
    )
    (net (code "115") (name "unconnected-(U$1-PE13-PadP$31)") (class "Default")
      (node (ref "U$1") (pin "P$31") (pinfunction "PE13_P$31") (pintype "bidirectional"))
    )
    (net (code "116") (name "unconnected-(U$1-PE14-PadP$32)") (class "Default")
      (node (ref "U$1") (pin "P$32") (pinfunction "PE14_P$32") (pintype "bidirectional"))
    )
    (net (code "117") (name "unconnected-(U$1-PE15-PadP$33)") (class "Default")
      (node (ref "U$1") (pin "P$33") (pinfunction "PE15_P$33") (pintype "bidirectional"))
    )
    (net (code "118") (name "unconnected-(U$1-PH0-PadP$57)") (class "Default")
      (node (ref "U$1") (pin "P$57") (pinfunction "PH0_P$57") (pintype "bidirectional"))
    )
    (net (code "119") (name "unconnected-(U$1-PH1-PadP$58)") (class "Default")
      (node (ref "U$1") (pin "P$58") (pinfunction "PH1_P$58") (pintype "bidirectional"))
    )
    (net (code "120") (name "unconnected-(U$1-VDD-PadP$3)") (class "Default")
      (node (ref "U$1") (pin "P$3") (pinfunction "VDD_P$3") (pintype "bidirectional"))
    )
    (net (code "121") (name "unconnected-(U$1-VDD1-PadP$4)") (class "Default")
      (node (ref "U$1") (pin "P$4") (pinfunction "VDD1_P$4") (pintype "bidirectional"))
    )
    (net (code "122") (name "unconnected-(U$1-VDD2-PadP$55)") (class "Default")
      (node (ref "U$1") (pin "P$55") (pinfunction "VDD2_P$55") (pintype "bidirectional"))
    )
    (net (code "123") (name "unconnected-(U$1-VDD3-PadP$56)") (class "Default")
      (node (ref "U$1") (pin "P$56") (pinfunction "VDD3_P$56") (pintype "bidirectional"))
    )
    (net (code "124") (name "unconnected-(U$1-VDD4-PadP$72)") (class "Default")
      (node (ref "U$1") (pin "P$72") (pinfunction "VDD4_P$72") (pintype "bidirectional"))
    )
  )
)
